# rel-prog-counter.net
KiCad netlist of a schematic drawn in EAGLE
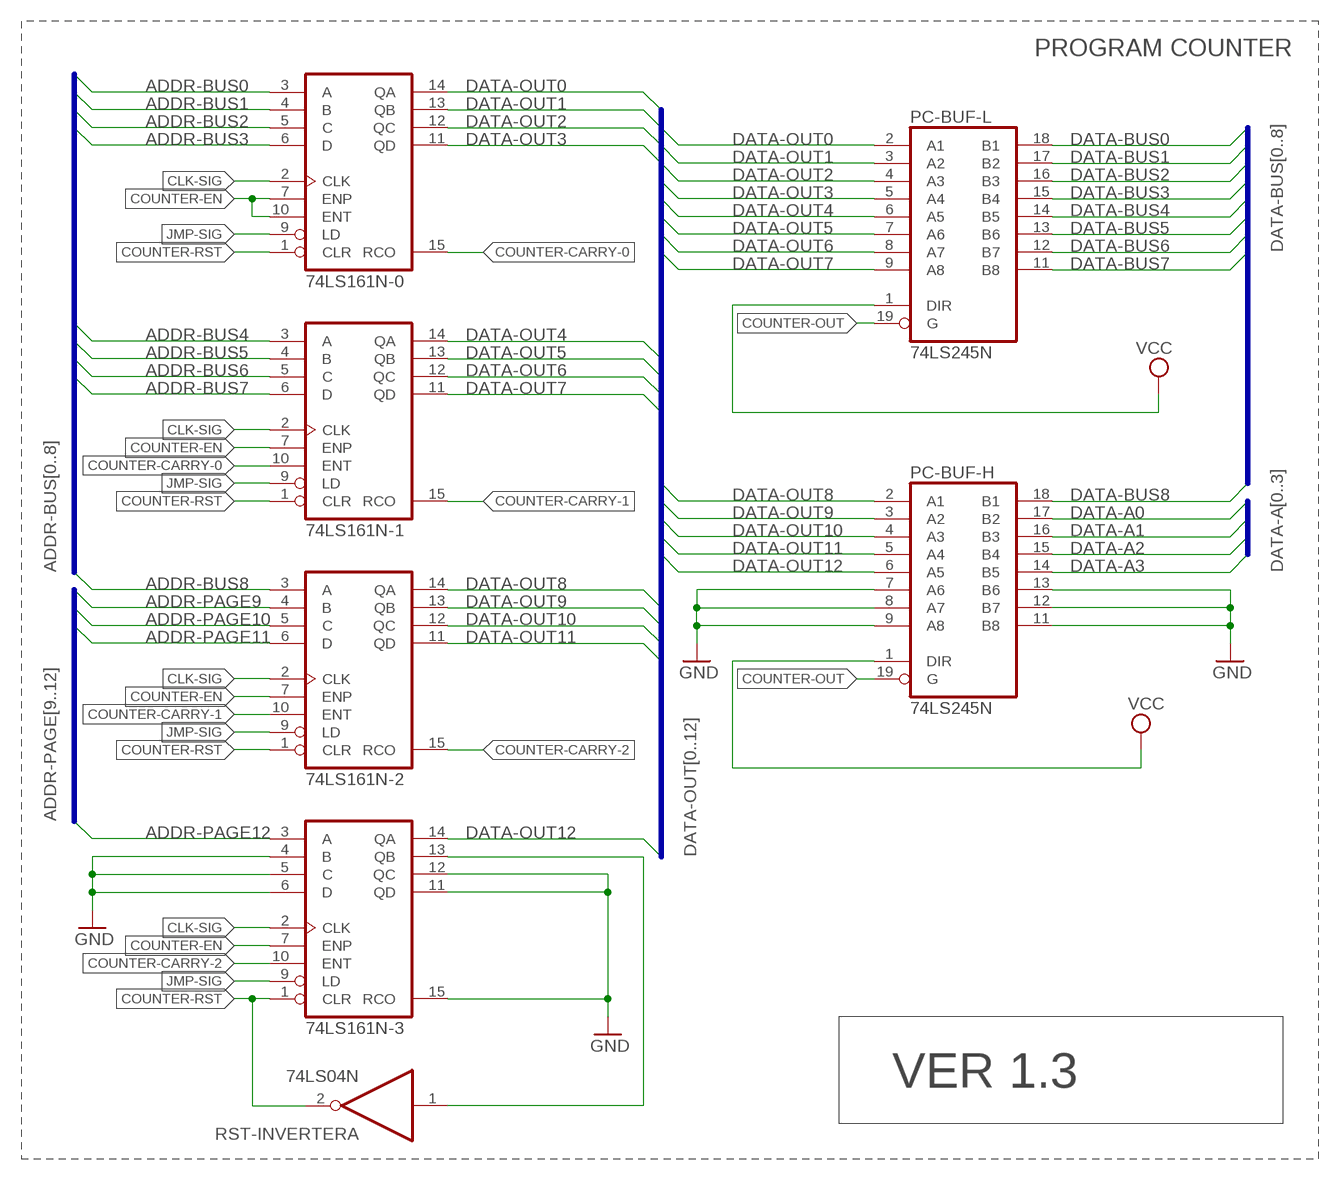
[diagram p0: schematic, sheet 1]

(export (version "E")
  (design (tool "Eeschema 10.0.6"))
  (components
    (comp (ref "74LS161N-0")
      (value "74160N")
      (footprint "eagle-import:DIL16")
      (libsource (lib "eagle-import") (part "74160N"))
    )
    (comp (ref "74LS161N-1")
      (value "74160N")
      (footprint "eagle-import:DIL16")
      (libsource (lib "eagle-import") (part "74160N"))
    )
    (comp (ref "74LS161N-2")
      (value "74160N")
      (footprint "eagle-import:DIL16")
      (libsource (lib "eagle-import") (part "74160N"))
    )
    (comp (ref "74LS161N-3")
      (value "74160N")
      (footprint "eagle-import:DIL16")
      (libsource (lib "eagle-import") (part "74160N"))
    )
    (comp (ref "PC-BUF-H")
      (value "74LS245N")
      (footprint "eagle-import:DIL20")
      (libsource (lib "eagle-import") (part "74245NLS"))
    )
    (comp (ref "PC-BUF-L")
      (value "74LS245N")
      (footprint "eagle-import:DIL20")
      (libsource (lib "eagle-import") (part "74245NLS"))
    )
    (comp (ref "RST-INVERTER")
      (value "74LS04N")
      (footprint "eagle-import:DIL14")
      (libsource (lib "eagle-import") (part "7404NLS"))
    )
  )
  (nets
    (net (code "1") (name "/ADDR-BUS0") (class "Default")
      (node (ref "74LS161N-0") (pin "3") (pinfunction "A_3") (pintype "input"))
    )
    (net (code "2") (name "/ADDR-BUS1") (class "Default")
      (node (ref "74LS161N-0") (pin "4") (pinfunction "B_4") (pintype "input"))
    )
    (net (code "3") (name "/ADDR-BUS2") (class "Default")
      (node (ref "74LS161N-0") (pin "5") (pinfunction "C_5") (pintype "input"))
    )
    (net (code "4") (name "/ADDR-BUS3") (class "Default")
      (node (ref "74LS161N-0") (pin "6") (pinfunction "D_6") (pintype "input"))
    )
    (net (code "5") (name "/ADDR-BUS4") (class "Default")
      (node (ref "74LS161N-1") (pin "3") (pinfunction "A_3") (pintype "input"))
    )
    (net (code "6") (name "/ADDR-BUS5") (class "Default")
      (node (ref "74LS161N-1") (pin "4") (pinfunction "B_4") (pintype "input"))
    )
    (net (code "7") (name "/ADDR-BUS6") (class "Default")
      (node (ref "74LS161N-1") (pin "5") (pinfunction "C_5") (pintype "input"))
    )
    (net (code "8") (name "/ADDR-BUS7") (class "Default")
      (node (ref "74LS161N-1") (pin "6") (pinfunction "D_6") (pintype "input"))
    )
    (net (code "9") (name "/ADDR-BUS8") (class "Default")
      (node (ref "74LS161N-2") (pin "3") (pinfunction "A_3") (pintype "input"))
    )
    (net (code "11") (name "/ADDR-PAGE9") (class "Default")
      (node (ref "74LS161N-2") (pin "4") (pinfunction "B_4") (pintype "input"))
    )
    (net (code "12") (name "/ADDR-PAGE10") (class "Default")
      (node (ref "74LS161N-2") (pin "5") (pinfunction "C_5") (pintype "input"))
    )
    (net (code "13") (name "/ADDR-PAGE11") (class "Default")
      (node (ref "74LS161N-2") (pin "6") (pinfunction "D_6") (pintype "input"))
    )
    (net (code "14") (name "/ADDR-PAGE12") (class "Default")
      (node (ref "74LS161N-3") (pin "3") (pinfunction "A_3") (pintype "input"))
    )
    (net (code "16") (name "/DATA-A0") (class "Default")
      (node (ref "PC-BUF-H") (pin "17") (pinfunction "B2_17") (pintype "bidirectional"))
    )
    (net (code "17") (name "/DATA-A1") (class "Default")
      (node (ref "PC-BUF-H") (pin "16") (pinfunction "B3_16") (pintype "bidirectional"))
    )
    (net (code "18") (name "/DATA-A2") (class "Default")
      (node (ref "PC-BUF-H") (pin "15") (pinfunction "B4_15") (pintype "bidirectional"))
    )
    (net (code "19") (name "/DATA-A3") (class "Default")
      (node (ref "PC-BUF-H") (pin "14") (pinfunction "B5_14") (pintype "bidirectional"))
    )
    (net (code "21") (name "/DATA-BUS0") (class "Default")
      (node (ref "PC-BUF-L") (pin "18") (pinfunction "B1_18") (pintype "bidirectional"))
    )
    (net (code "22") (name "/DATA-BUS1") (class "Default")
      (node (ref "PC-BUF-L") (pin "17") (pinfunction "B2_17") (pintype "bidirectional"))
    )
    (net (code "23") (name "/DATA-BUS2") (class "Default")
      (node (ref "PC-BUF-L") (pin "16") (pinfunction "B3_16") (pintype "bidirectional"))
    )
    (net (code "24") (name "/DATA-BUS3") (class "Default")
      (node (ref "PC-BUF-L") (pin "15") (pinfunction "B4_15") (pintype "bidirectional"))
    )
    (net (code "25") (name "/DATA-BUS4") (class "Default")
      (node (ref "PC-BUF-L") (pin "14") (pinfunction "B5_14") (pintype "bidirectional"))
    )
    (net (code "26") (name "/DATA-BUS5") (class "Default")
      (node (ref "PC-BUF-L") (pin "13") (pinfunction "B6_13") (pintype "bidirectional"))
    )
    (net (code "27") (name "/DATA-BUS6") (class "Default")
      (node (ref "PC-BUF-L") (pin "12") (pinfunction "B7_12") (pintype "bidirectional"))
    )
    (net (code "28") (name "/DATA-BUS7") (class "Default")
      (node (ref "PC-BUF-L") (pin "11") (pinfunction "B8_11") (pintype "bidirectional"))
    )
    (net (code "29") (name "/DATA-BUS8") (class "Default")
      (node (ref "PC-BUF-H") (pin "18") (pinfunction "B1_18") (pintype "bidirectional"))
    )
    (net (code "31") (name "/DATA-OUT0") (class "Default")
      (node (ref "74LS161N-0") (pin "14") (pinfunction "QA_14") (pintype "output"))
      (node (ref "PC-BUF-L") (pin "2") (pinfunction "A1_2") (pintype "bidirectional"))
    )
    (net (code "32") (name "/DATA-OUT1") (class "Default")
      (node (ref "74LS161N-0") (pin "13") (pinfunction "QB_13") (pintype "output"))
      (node (ref "PC-BUF-L") (pin "3") (pinfunction "A2_3") (pintype "bidirectional"))
    )
    (net (code "33") (name "/DATA-OUT2") (class "Default")
      (node (ref "74LS161N-0") (pin "12") (pinfunction "QC_12") (pintype "output"))
      (node (ref "PC-BUF-L") (pin "4") (pinfunction "A3_4") (pintype "bidirectional"))
    )
    (net (code "34") (name "/DATA-OUT3") (class "Default")
      (node (ref "74LS161N-0") (pin "11") (pinfunction "QD_11") (pintype "output"))
      (node (ref "PC-BUF-L") (pin "5") (pinfunction "A4_5") (pintype "bidirectional"))
    )
    (net (code "35") (name "/DATA-OUT4") (class "Default")
      (node (ref "74LS161N-1") (pin "14") (pinfunction "QA_14") (pintype "output"))
      (node (ref "PC-BUF-L") (pin "6") (pinfunction "A5_6") (pintype "bidirectional"))
    )
    (net (code "36") (name "/DATA-OUT5") (class "Default")
      (node (ref "74LS161N-1") (pin "13") (pinfunction "QB_13") (pintype "output"))
      (node (ref "PC-BUF-L") (pin "7") (pinfunction "A6_7") (pintype "bidirectional"))
    )
    (net (code "37") (name "/DATA-OUT6") (class "Default")
      (node (ref "74LS161N-1") (pin "12") (pinfunction "QC_12") (pintype "output"))
      (node (ref "PC-BUF-L") (pin "8") (pinfunction "A7_8") (pintype "bidirectional"))
    )
    (net (code "38") (name "/DATA-OUT7") (class "Default")
      (node (ref "74LS161N-1") (pin "11") (pinfunction "QD_11") (pintype "output"))
      (node (ref "PC-BUF-L") (pin "9") (pinfunction "A8_9") (pintype "bidirectional"))
    )
    (net (code "39") (name "/DATA-OUT8") (class "Default")
      (node (ref "74LS161N-2") (pin "14") (pinfunction "QA_14") (pintype "output"))
      (node (ref "PC-BUF-H") (pin "2") (pinfunction "A1_2") (pintype "bidirectional"))
    )
    (net (code "40") (name "/DATA-OUT9") (class "Default")
      (node (ref "74LS161N-2") (pin "13") (pinfunction "QB_13") (pintype "output"))
      (node (ref "PC-BUF-H") (pin "3") (pinfunction "A2_3") (pintype "bidirectional"))
    )
    (net (code "41") (name "/DATA-OUT10") (class "Default")
      (node (ref "74LS161N-2") (pin "12") (pinfunction "QC_12") (pintype "output"))
      (node (ref "PC-BUF-H") (pin "4") (pinfunction "A3_4") (pintype "bidirectional"))
    )
    (net (code "42") (name "/DATA-OUT11") (class "Default")
      (node (ref "74LS161N-2") (pin "11") (pinfunction "QD_11") (pintype "output"))
      (node (ref "PC-BUF-H") (pin "5") (pinfunction "A4_5") (pintype "bidirectional"))
    )
    (net (code "43") (name "/DATA-OUT12") (class "Default")
      (node (ref "74LS161N-3") (pin "14") (pinfunction "QA_14") (pintype "output"))
      (node (ref "PC-BUF-H") (pin "6") (pinfunction "A5_6") (pintype "bidirectional"))
    )
    (net (code "45") (name "CLK-SIG") (class "Default")
      (node (ref "74LS161N-0") (pin "2") (pinfunction "CLK_2") (pintype "input"))
      (node (ref "74LS161N-1") (pin "2") (pinfunction "CLK_2") (pintype "input"))
      (node (ref "74LS161N-2") (pin "2") (pinfunction "CLK_2") (pintype "input"))
      (node (ref "74LS161N-3") (pin "2") (pinfunction "CLK_2") (pintype "input"))
    )
    (net (code "46") (name "COUNTER-CARRY-0") (class "Default")
      (node (ref "74LS161N-0") (pin "15") (pinfunction "RCO_15") (pintype "output"))
      (node (ref "74LS161N-1") (pin "10") (pinfunction "ENT_10") (pintype "input"))
    )
    (net (code "47") (name "COUNTER-CARRY-1") (class "Default")
      (node (ref "74LS161N-1") (pin "15") (pinfunction "RCO_15") (pintype "output"))
      (node (ref "74LS161N-2") (pin "10") (pinfunction "ENT_10") (pintype "input"))
    )
    (net (code "48") (name "COUNTER-CARRY-2") (class "Default")
      (node (ref "74LS161N-2") (pin "15") (pinfunction "RCO_15") (pintype "output"))
      (node (ref "74LS161N-3") (pin "10") (pinfunction "ENT_10") (pintype "input"))
    )
    (net (code "49") (name "COUNTER-EN") (class "Default")
      (node (ref "74LS161N-0") (pin "10") (pinfunction "ENT_10") (pintype "input"))
      (node (ref "74LS161N-0") (pin "7") (pinfunction "ENP_7") (pintype "input"))
      (node (ref "74LS161N-1") (pin "7") (pinfunction "ENP_7") (pintype "input"))
      (node (ref "74LS161N-2") (pin "7") (pinfunction "ENP_7") (pintype "input"))
      (node (ref "74LS161N-3") (pin "7") (pinfunction "ENP_7") (pintype "input"))
    )
    (net (code "50") (name "COUNTER-OUT") (class "Default")
      (node (ref "PC-BUF-H") (pin "19") (pinfunction "G_19") (pintype "input"))
      (node (ref "PC-BUF-L") (pin "19") (pinfunction "G_19") (pintype "input"))
    )
    (net (code "51") (name "COUNTER-RST") (class "Default")
      (node (ref "74LS161N-0") (pin "1") (pinfunction "CLR_1") (pintype "input"))
      (node (ref "74LS161N-1") (pin "1") (pinfunction "CLR_1") (pintype "input"))
      (node (ref "74LS161N-2") (pin "1") (pinfunction "CLR_1") (pintype "input"))
      (node (ref "74LS161N-3") (pin "1") (pinfunction "CLR_1") (pintype "input"))
      (node (ref "RST-INVERTER") (pin "2") (pinfunction "O_2") (pintype "output"))
    )
    (net (code "52") (name "GND") (class "Default")
      (node (ref "74LS161N-3") (pin "11") (pinfunction "QD_11") (pintype "output"))
      (node (ref "74LS161N-3") (pin "12") (pinfunction "QC_12") (pintype "output"))
      (node (ref "74LS161N-3") (pin "15") (pinfunction "RCO_15") (pintype "output"))
      (node (ref "74LS161N-3") (pin "4") (pinfunction "B_4") (pintype "input"))
      (node (ref "74LS161N-3") (pin "5") (pinfunction "C_5") (pintype "input"))
      (node (ref "74LS161N-3") (pin "6") (pinfunction "D_6") (pintype "input"))
      (node (ref "PC-BUF-H") (pin "11") (pinfunction "B8_11") (pintype "bidirectional"))
      (node (ref "PC-BUF-H") (pin "12") (pinfunction "B7_12") (pintype "bidirectional"))
      (node (ref "PC-BUF-H") (pin "13") (pinfunction "B6_13") (pintype "bidirectional"))
      (node (ref "PC-BUF-H") (pin "7") (pinfunction "A6_7") (pintype "bidirectional"))
      (node (ref "PC-BUF-H") (pin "8") (pinfunction "A7_8") (pintype "bidirectional"))
      (node (ref "PC-BUF-H") (pin "9") (pinfunction "A8_9") (pintype "bidirectional"))
    )
    (net (code "53") (name "JMP-SIG") (class "Default")
      (node (ref "74LS161N-0") (pin "9") (pinfunction "LD_9") (pintype "input"))
      (node (ref "74LS161N-1") (pin "9") (pinfunction "LD_9") (pintype "input"))
      (node (ref "74LS161N-2") (pin "9") (pinfunction "LD_9") (pintype "input"))
      (node (ref "74LS161N-3") (pin "9") (pinfunction "LD_9") (pintype "input"))
    )
    (net (code "54") (name "Net-(74LS161N-3A-QB)") (class "Default")
      (node (ref "74LS161N-3") (pin "13") (pinfunction "QB_13") (pintype "output"))
      (node (ref "RST-INVERTER") (pin "1") (pinfunction "I_1") (pintype "input"))
    )
    (net (code "55") (name "VCC") (class "Default")
      (node (ref "PC-BUF-H") (pin "1") (pinfunction "DIR_1") (pintype "input"))
      (node (ref "PC-BUF-L") (pin "1") (pinfunction "DIR_1") (pintype "input"))
    )
  )
)
